# v2164_quad_VC_mixer_0402_DIL.net
KiCad netlist of a schematic drawn in EAGLE
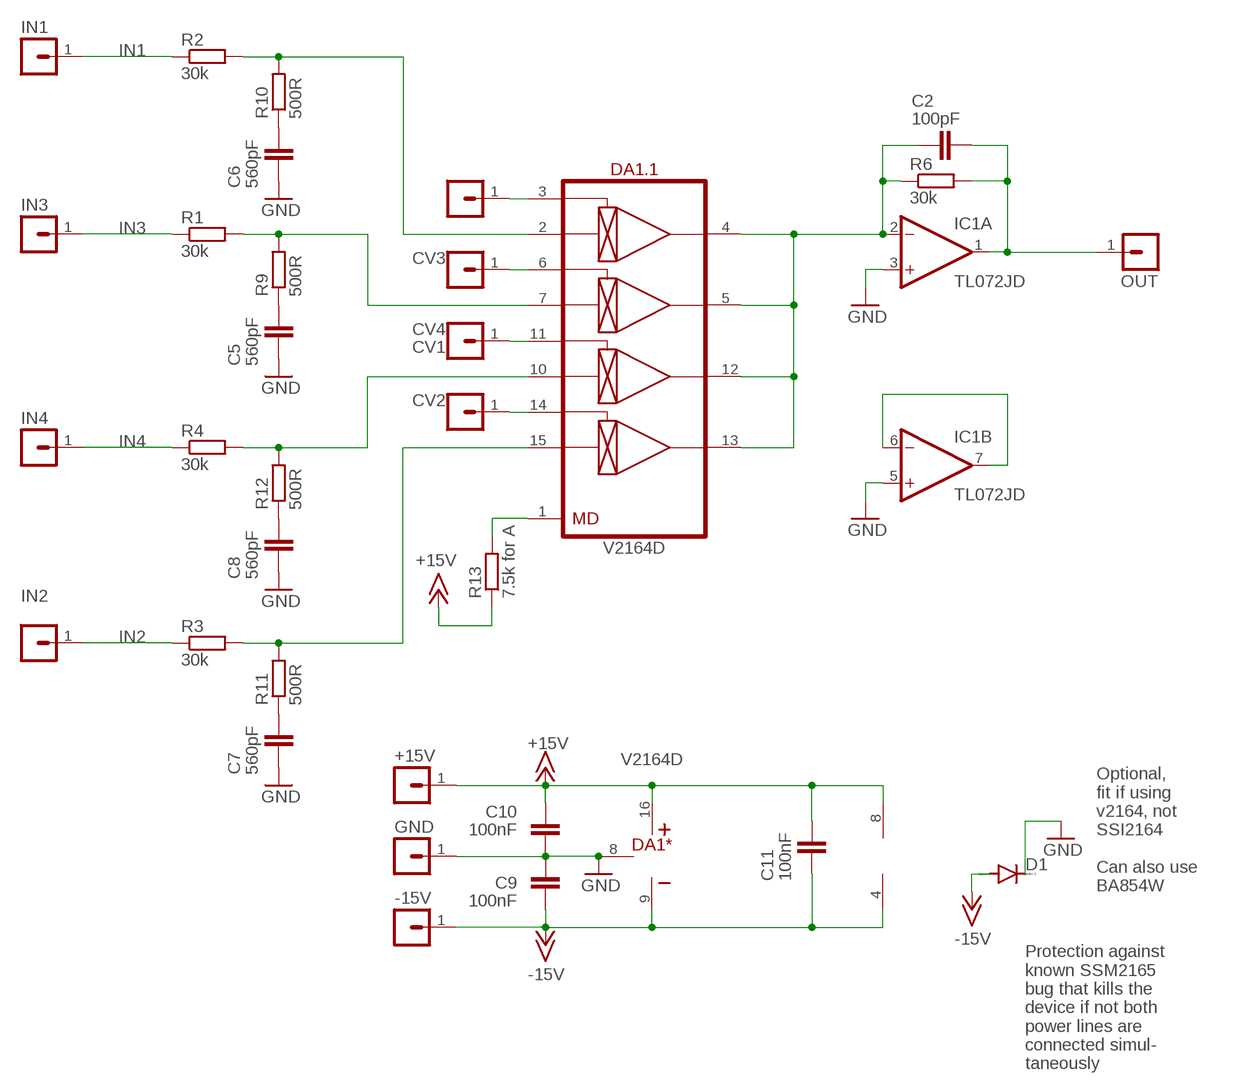
[diagram p0: schematic, sheet 1]

(export (version "E")
  (design (tool "Eeschema 10.0.6"))
  (components
    (comp (ref "+15V")
      (value "MA01-1JP")
      (footprint "eagle-import:SIP-PIN01-1J")
      (libsource (lib "eagle-import") (part "MA01-1JP"))
    )
    (comp (ref "-15V")
      (value "MA01-1JP")
      (footprint "eagle-import:SIP-PIN01-1J")
      (libsource (lib "eagle-import") (part "MA01-1JP"))
    )
    (comp (ref "C2")
      (value "100pF")
      (footprint "eagle-import:C0402")
      (libsource (lib "eagle-import") (part "C-EUC0402"))
    )
    (comp (ref "C5")
      (value "560pF")
      (footprint "eagle-import:C0603")
      (libsource (lib "eagle-import") (part "C-EUC0603"))
    )
    (comp (ref "C6")
      (value "560pF")
      (footprint "eagle-import:C0603")
      (libsource (lib "eagle-import") (part "C-EUC0603"))
    )
    (comp (ref "C7")
      (value "560pF")
      (footprint "eagle-import:C0603")
      (libsource (lib "eagle-import") (part "C-EUC0603"))
    )
    (comp (ref "C8")
      (value "560pF")
      (footprint "eagle-import:C0603")
      (libsource (lib "eagle-import") (part "C-EUC0603"))
    )
    (comp (ref "C9")
      (value "100nF")
      (footprint "eagle-import:C0402")
      (libsource (lib "eagle-import") (part "C-EUC0402"))
    )
    (comp (ref "C10")
      (value "100nF")
      (footprint "eagle-import:C0402")
      (libsource (lib "eagle-import") (part "C-EUC0402"))
    )
    (comp (ref "C11")
      (value "100nF")
      (footprint "eagle-import:C0402")
      (libsource (lib "eagle-import") (part "C-EUC0402"))
    )
    (comp (ref "CV1")
      (value "MA01-1JP")
      (footprint "eagle-import:SIP-PIN01-1J")
      (libsource (lib "eagle-import") (part "MA01-1JP"))
    )
    (comp (ref "CV2")
      (value "MA01-1JP")
      (footprint "eagle-import:SIP-PIN01-1J")
      (libsource (lib "eagle-import") (part "MA01-1JP"))
    )
    (comp (ref "CV3")
      (value "MA01-1JP")
      (footprint "eagle-import:SIP-PIN01-1J")
      (libsource (lib "eagle-import") (part "MA01-1JP"))
    )
    (comp (ref "CV4")
      (value "MA01-1JP")
      (footprint "eagle-import:SIP-PIN01-1J")
      (libsource (lib "eagle-import") (part "MA01-1JP"))
    )
    (comp (ref "D1")
      (value "DIODE-SOD323-R")
      (footprint "eagle-import:SOD323-R")
      (libsource (lib "eagle-import") (part "DIODE-SOD323-R"))
    )
    (comp (ref "DA1")
      (value "V2164D")
      (footprint "eagle-import:DIP-16")
      (libsource (lib "eagle-import") (part "V2164D"))
    )
    (comp (ref "GND")
      (value "MA01-1JP")
      (footprint "eagle-import:SIP-PIN01-1J")
      (libsource (lib "eagle-import") (part "MA01-1JP"))
    )
    (comp (ref "IC1")
      (value "TL072JD")
      (footprint "eagle-import:SO08J")
      (libsource (lib "eagle-import") (part "TL072JD"))
    )
    (comp (ref "IN1")
      (value "MA01-1JP")
      (footprint "eagle-import:SIP-PIN01-1J")
      (libsource (lib "eagle-import") (part "MA01-1JP"))
    )
    (comp (ref "IN2")
      (value "MA01-1JP")
      (footprint "eagle-import:SIP-PIN01-1J")
      (libsource (lib "eagle-import") (part "MA01-1JP"))
    )
    (comp (ref "IN3")
      (value "MA01-1JP")
      (footprint "eagle-import:SIP-PIN01-1J")
      (libsource (lib "eagle-import") (part "MA01-1JP"))
    )
    (comp (ref "IN4")
      (value "MA01-1JP")
      (footprint "eagle-import:SIP-PIN01-1J")
      (libsource (lib "eagle-import") (part "MA01-1JP"))
    )
    (comp (ref "OUT")
      (value "MA01-1JP")
      (footprint "eagle-import:SIP-PIN01-1J")
      (libsource (lib "eagle-import") (part "MA01-1JP"))
    )
    (comp (ref "R1")
      (value "30k")
      (footprint "eagle-import:R0402")
      (libsource (lib "eagle-import") (part "R-EU_R0402"))
    )
    (comp (ref "R2")
      (value "30k")
      (footprint "eagle-import:R0402")
      (libsource (lib "eagle-import") (part "R-EU_R0402"))
    )
    (comp (ref "R3")
      (value "30k")
      (footprint "eagle-import:R0402")
      (libsource (lib "eagle-import") (part "R-EU_R0402"))
    )
    (comp (ref "R4")
      (value "30k")
      (footprint "eagle-import:R0402")
      (libsource (lib "eagle-import") (part "R-EU_R0402"))
    )
    (comp (ref "R6")
      (value "30k")
      (footprint "eagle-import:R0402")
      (libsource (lib "eagle-import") (part "R-EU_R0402"))
    )
    (comp (ref "R9")
      (value "500R")
      (footprint "eagle-import:R0402")
      (libsource (lib "eagle-import") (part "R-EU_R0402"))
    )
    (comp (ref "R10")
      (value "500R")
      (footprint "eagle-import:R0402")
      (libsource (lib "eagle-import") (part "R-EU_R0402"))
    )
    (comp (ref "R11")
      (value "500R")
      (footprint "eagle-import:R0402")
      (libsource (lib "eagle-import") (part "R-EU_R0402"))
    )
    (comp (ref "R12")
      (value "500R")
      (footprint "eagle-import:R0402")
      (libsource (lib "eagle-import") (part "R-EU_R0402"))
    )
    (comp (ref "R13")
      (value "7.5k for A")
      (footprint "eagle-import:R0402")
      (libsource (lib "eagle-import") (part "R-EU_R0402"))
    )
  )
  (nets
    (net (code "1") (name "+15V") (class "Default")
      (node (ref "+15V") (pin "1") (pinfunction "1_1") (pintype "passive"))
      (node (ref "C10") (pin "2") (pinfunction "2_2") (pintype "passive"))
      (node (ref "C11") (pin "2") (pinfunction "2_2") (pintype "passive"))
      (node (ref "DA1") (pin "16") (pinfunction "V+_16") (pintype "power_in"))
      (node (ref "IC1") (pin "8") (pinfunction "V+_8") (pintype "power_in"))
      (node (ref "R13") (pin "1") (pinfunction "1_1") (pintype "passive"))
    )
    (net (code "2") (name "-15V") (class "Default")
      (node (ref "-15V") (pin "1") (pinfunction "1_1") (pintype "passive"))
      (node (ref "C11") (pin "1") (pinfunction "1_1") (pintype "passive"))
      (node (ref "C9") (pin "1") (pinfunction "1_1") (pintype "passive"))
      (node (ref "D1") (pin "A") (pinfunction "A_A") (pintype "passive"))
      (node (ref "DA1") (pin "9") (pinfunction "V-_9") (pintype "power_in"))
      (node (ref "IC1") (pin "4") (pinfunction "V-_4") (pintype "power_in"))
    )
    (net (code "3") (name "/IN1") (class "Default")
      (node (ref "IN1") (pin "1") (pinfunction "1_1") (pintype "passive"))
      (node (ref "R2") (pin "1") (pinfunction "1_1") (pintype "passive"))
    )
    (net (code "4") (name "/IN2") (class "Default")
      (node (ref "IN2") (pin "1") (pinfunction "1_1") (pintype "passive"))
      (node (ref "R3") (pin "1") (pinfunction "1_1") (pintype "passive"))
    )
    (net (code "5") (name "/IN3") (class "Default")
      (node (ref "IN3") (pin "1") (pinfunction "1_1") (pintype "passive"))
      (node (ref "R1") (pin "1") (pinfunction "1_1") (pintype "passive"))
    )
    (net (code "6") (name "/IN4") (class "Default")
      (node (ref "IN4") (pin "1") (pinfunction "1_1") (pintype "passive"))
      (node (ref "R4") (pin "1") (pinfunction "1_1") (pintype "passive"))
    )
    (net (code "7") (name "GND") (class "Default")
      (node (ref "C10") (pin "1") (pinfunction "1_1") (pintype "passive"))
      (node (ref "C5") (pin "1") (pinfunction "1_1") (pintype "passive"))
      (node (ref "C6") (pin "1") (pinfunction "1_1") (pintype "passive"))
      (node (ref "C7") (pin "1") (pinfunction "1_1") (pintype "passive"))
      (node (ref "C8") (pin "1") (pinfunction "1_1") (pintype "passive"))
      (node (ref "C9") (pin "2") (pinfunction "2_2") (pintype "passive"))
      (node (ref "D1") (pin "C") (pinfunction "C_C") (pintype "passive"))
      (node (ref "DA1") (pin "8") (pinfunction "GND_8") (pintype "power_in"))
      (node (ref "GND") (pin "1") (pinfunction "1_1") (pintype "passive"))
      (node (ref "IC1") (pin "3") (pinfunction "+IN_3") (pintype "input"))
      (node (ref "IC1") (pin "5") (pinfunction "+IN_5") (pintype "input"))
    )
    (net (code "8") (name "Net-(C5-Pad2)") (class "Default")
      (node (ref "C5") (pin "2") (pinfunction "2_2") (pintype "passive"))
      (node (ref "R9") (pin "1") (pinfunction "1_1") (pintype "passive"))
    )
    (net (code "9") (name "Net-(C6-Pad2)") (class "Default")
      (node (ref "C6") (pin "2") (pinfunction "2_2") (pintype "passive"))
      (node (ref "R10") (pin "1") (pinfunction "1_1") (pintype "passive"))
    )
    (net (code "10") (name "Net-(C7-Pad2)") (class "Default")
      (node (ref "C7") (pin "2") (pinfunction "2_2") (pintype "passive"))
      (node (ref "R11") (pin "1") (pinfunction "1_1") (pintype "passive"))
    )
    (net (code "11") (name "Net-(C8-Pad2)") (class "Default")
      (node (ref "C8") (pin "2") (pinfunction "2_2") (pintype "passive"))
      (node (ref "R12") (pin "1") (pinfunction "1_1") (pintype "passive"))
    )
    (net (code "12") (name "Net-(DA1B-CV1)") (class "Default")
      (node (ref "CV1") (pin "1") (pinfunction "1_1") (pintype "passive"))
      (node (ref "DA1") (pin "3") (pinfunction "CV1_3") (pintype "input"))
    )
    (net (code "13") (name "Net-(DA1B-CV2)") (class "Default")
      (node (ref "CV3") (pin "1") (pinfunction "1_1") (pintype "passive"))
      (node (ref "DA1") (pin "6") (pinfunction "CV2_6") (pintype "input"))
    )
    (net (code "14") (name "Net-(DA1B-CV3)") (class "Default")
      (node (ref "CV4") (pin "1") (pinfunction "1_1") (pintype "passive"))
      (node (ref "DA1") (pin "11") (pinfunction "CV3_11") (pintype "input"))
    )
    (net (code "15") (name "Net-(DA1B-CV4)") (class "Default")
      (node (ref "CV2") (pin "1") (pinfunction "1_1") (pintype "passive"))
      (node (ref "DA1") (pin "14") (pinfunction "CV4_14") (pintype "input"))
    )
    (net (code "16") (name "Net-(DA1B-IN1)") (class "Default")
      (node (ref "DA1") (pin "2") (pinfunction "IN1_2") (pintype "input"))
      (node (ref "R10") (pin "2") (pinfunction "2_2") (pintype "passive"))
      (node (ref "R2") (pin "2") (pinfunction "2_2") (pintype "passive"))
    )
    (net (code "17") (name "Net-(DA1B-IN2)") (class "Default")
      (node (ref "DA1") (pin "7") (pinfunction "IN2_7") (pintype "input"))
      (node (ref "R1") (pin "2") (pinfunction "2_2") (pintype "passive"))
      (node (ref "R9") (pin "2") (pinfunction "2_2") (pintype "passive"))
    )
    (net (code "18") (name "Net-(DA1B-IN3)") (class "Default")
      (node (ref "DA1") (pin "10") (pinfunction "IN3_10") (pintype "input"))
      (node (ref "R12") (pin "2") (pinfunction "2_2") (pintype "passive"))
      (node (ref "R4") (pin "2") (pinfunction "2_2") (pintype "passive"))
    )
    (net (code "19") (name "Net-(DA1B-IN4)") (class "Default")
      (node (ref "DA1") (pin "15") (pinfunction "IN4_15") (pintype "input"))
      (node (ref "R11") (pin "2") (pinfunction "2_2") (pintype "passive"))
      (node (ref "R3") (pin "2") (pinfunction "2_2") (pintype "passive"))
    )
    (net (code "20") (name "Net-(DA1B-MD)") (class "Default")
      (node (ref "DA1") (pin "1") (pinfunction "MD_1") (pintype "output"))
      (node (ref "R13") (pin "2") (pinfunction "2_2") (pintype "passive"))
    )
    (net (code "21") (name "Net-(DA1B-OUT1)") (class "Default")
      (node (ref "C2") (pin "1") (pinfunction "1_1") (pintype "passive"))
      (node (ref "DA1") (pin "12") (pinfunction "OUT3_12") (pintype "output"))
      (node (ref "DA1") (pin "13") (pinfunction "OUT4_13") (pintype "output"))
      (node (ref "DA1") (pin "4") (pinfunction "OUT1_4") (pintype "output"))
      (node (ref "DA1") (pin "5") (pinfunction "OUT2_5") (pintype "output"))
      (node (ref "IC1") (pin "2") (pinfunction "-IN_2") (pintype "input"))
      (node (ref "R6") (pin "1") (pinfunction "1_1") (pintype "passive"))
    )
    (net (code "22") (name "Net-(IC1A-OUT)") (class "Default")
      (node (ref "C2") (pin "2") (pinfunction "2_2") (pintype "passive"))
      (node (ref "IC1") (pin "1") (pinfunction "OUT_1") (pintype "output"))
      (node (ref "OUT") (pin "1") (pinfunction "1_1") (pintype "passive"))
      (node (ref "R6") (pin "2") (pinfunction "2_2") (pintype "passive"))
    )
    (net (code "23") (name "Net-(IC1B--IN)") (class "Default")
      (node (ref "IC1") (pin "6") (pinfunction "-IN_6") (pintype "input"))
      (node (ref "IC1") (pin "7") (pinfunction "OUT_7") (pintype "output"))
    )
  )
)
